# GS_V1.net
KiCad netlist of a schematic drawn in Altium Designer
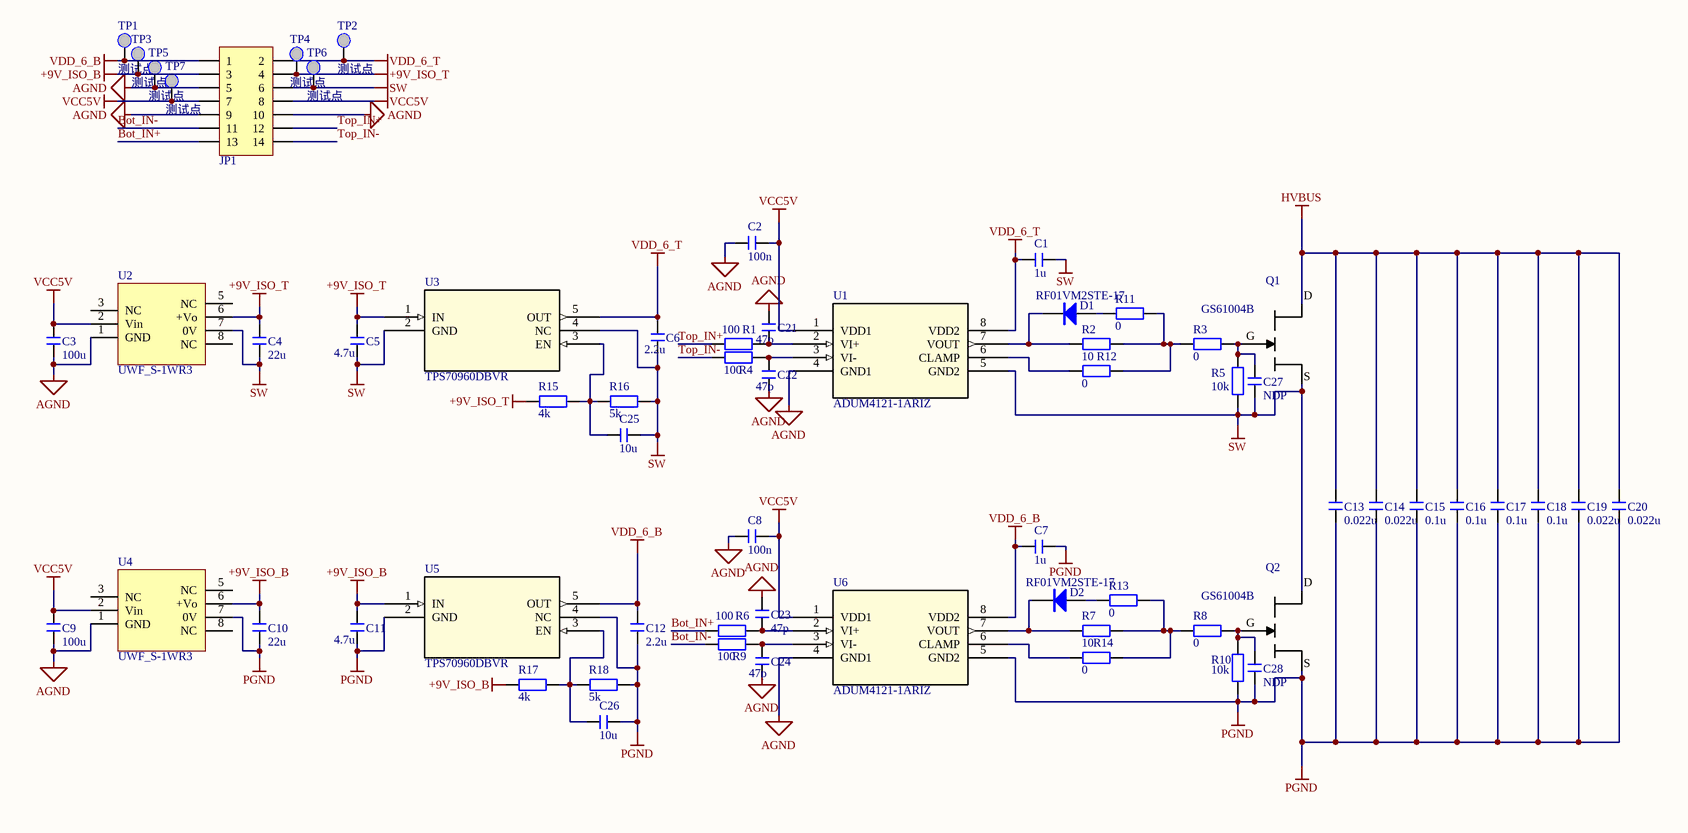
[diagram p0: GS_V1.SchDoc]

(export (version "E")
  (design (tool "Eeschema 10.0.6"))
  (components
    (comp (ref "C1")
      (value "1u")
      (footprint "C 0603_L")
      (description "无极性贴片电容")
      (fields (field (name "版权归属") "源创客"))
      (libsource (lib "3.1   - 电阻-电容-电感") (part "C"))
    )
    (comp (ref "C2")
      (value "100n")
      (footprint "C 0603_L")
      (description "无极性贴片电容")
      (fields (field (name "版权归属") "源创客"))
      (libsource (lib "3.1   - 电阻-电容-电感") (part "C"))
    )
    (comp (ref "C3")
      (value "100u")
      (footprint "C 0805_L")
      (description "无极性贴片电容")
      (fields (field (name "版权归属") "源创客"))
      (libsource (lib "3.1   - 电阻-电容-电感") (part "C"))
    )
    (comp (ref "C4")
      (value "22u")
      (footprint "C 0603_L")
      (description "无极性贴片电容")
      (fields (field (name "版权归属") "源创客"))
      (libsource (lib "3.1   - 电阻-电容-电感") (part "C"))
    )
    (comp (ref "C5")
      (value "4.7u")
      (footprint "C 0603_L")
      (description "无极性贴片电容")
      (fields (field (name "版权归属") "源创客"))
      (libsource (lib "3.1   - 电阻-电容-电感") (part "C"))
    )
    (comp (ref "C6")
      (value "2.2u")
      (footprint "C 0603_L")
      (description "无极性贴片电容")
      (fields (field (name "版权归属") "源创客"))
      (libsource (lib "3.1   - 电阻-电容-电感") (part "C"))
    )
    (comp (ref "C7")
      (value "1u")
      (footprint "C 0603_L")
      (description "无极性贴片电容")
      (fields (field (name "版权归属") "源创客"))
      (libsource (lib "3.1   - 电阻-电容-电感") (part "C"))
    )
    (comp (ref "C8")
      (value "100n")
      (footprint "C 0603_L")
      (description "无极性贴片电容")
      (fields (field (name "版权归属") "源创客"))
      (libsource (lib "3.1   - 电阻-电容-电感") (part "C"))
    )
    (comp (ref "C9")
      (value "100u")
      (footprint "C 0805_L")
      (description "无极性贴片电容")
      (fields (field (name "版权归属") "源创客"))
      (libsource (lib "3.1   - 电阻-电容-电感") (part "C"))
    )
    (comp (ref "C10")
      (value "22u")
      (footprint "C 0603_L")
      (description "无极性贴片电容")
      (fields (field (name "版权归属") "源创客"))
      (libsource (lib "3.1   - 电阻-电容-电感") (part "C"))
    )
    (comp (ref "C11")
      (value "4.7u")
      (footprint "C 0603_L")
      (description "无极性贴片电容")
      (fields (field (name "版权归属") "源创客"))
      (libsource (lib "3.1   - 电阻-电容-电感") (part "C"))
    )
    (comp (ref "C12")
      (value "2.2u")
      (footprint "C 0603_L")
      (description "无极性贴片电容")
      (fields (field (name "版权归属") "源创客"))
      (libsource (lib "3.1   - 电阻-电容-电感") (part "C"))
    )
    (comp (ref "C13")
      (value "0.022u")
      (footprint "C 0805_L")
      (description "无极性贴片电容")
      (fields (field (name "版权归属") "源创客"))
      (libsource (lib "3.1   - 电阻-电容-电感") (part "C"))
    )
    (comp (ref "C14")
      (value "0.022u")
      (footprint "C 0805_L")
      (description "无极性贴片电容")
      (fields (field (name "版权归属") "源创客"))
      (libsource (lib "3.1   - 电阻-电容-电感") (part "C"))
    )
    (comp (ref "C15")
      (value "0.1u")
      (footprint "C 0805_L")
      (description "无极性贴片电容")
      (fields (field (name "版权归属") "源创客"))
      (libsource (lib "3.1   - 电阻-电容-电感") (part "C"))
    )
    (comp (ref "C16")
      (value "0.1u")
      (footprint "C 0805_L")
      (description "无极性贴片电容")
      (fields (field (name "版权归属") "源创客"))
      (libsource (lib "3.1   - 电阻-电容-电感") (part "C"))
    )
    (comp (ref "C17")
      (value "0.1u")
      (footprint "C 0805_L")
      (description "无极性贴片电容")
      (fields (field (name "版权归属") "源创客"))
      (libsource (lib "3.1   - 电阻-电容-电感") (part "C"))
    )
    (comp (ref "C18")
      (value "0.1u")
      (footprint "C 0805_L")
      (description "无极性贴片电容")
      (fields (field (name "版权归属") "源创客"))
      (libsource (lib "3.1   - 电阻-电容-电感") (part "C"))
    )
    (comp (ref "C19")
      (value "0.022u")
      (footprint "C 0805_L")
      (description "无极性贴片电容")
      (fields (field (name "版权归属") "源创客"))
      (libsource (lib "3.1   - 电阻-电容-电感") (part "C"))
    )
    (comp (ref "C20")
      (value "0.022u")
      (footprint "C 0805_L")
      (description "无极性贴片电容")
      (fields (field (name "版权归属") "源创客"))
      (libsource (lib "3.1   - 电阻-电容-电感") (part "C"))
    )
    (comp (ref "C21")
      (value "47p")
      (footprint "C 0603_L")
      (description "无极性贴片电容")
      (fields (field (name "版权归属") "源创客"))
      (libsource (lib "3.1   - 电阻-电容-电感") (part "C"))
    )
    (comp (ref "C22")
      (value "47p")
      (footprint "C 0603_L")
      (description "无极性贴片电容")
      (fields (field (name "版权归属") "源创客"))
      (libsource (lib "3.1   - 电阻-电容-电感") (part "C"))
    )
    (comp (ref "C23")
      (value "47p")
      (footprint "C 0603_L")
      (description "无极性贴片电容")
      (fields (field (name "版权归属") "源创客"))
      (libsource (lib "3.1   - 电阻-电容-电感") (part "C"))
    )
    (comp (ref "C24")
      (value "47p")
      (footprint "C 0603_L")
      (description "无极性贴片电容")
      (fields (field (name "版权归属") "源创客"))
      (libsource (lib "3.1   - 电阻-电容-电感") (part "C"))
    )
    (comp (ref "C25")
      (value "10u")
      (footprint "C 0603_L")
      (description "无极性贴片电容")
      (fields (field (name "版权归属") "源创客"))
      (libsource (lib "3.1   - 电阻-电容-电感") (part "C"))
    )
    (comp (ref "C26")
      (value "10u")
      (footprint "C 0603_L")
      (description "无极性贴片电容")
      (fields (field (name "版权归属") "源创客"))
      (libsource (lib "3.1   - 电阻-电容-电感") (part "C"))
    )
    (comp (ref "C27")
      (value "NDP")
      (footprint "C 0603_L")
      (description "无极性贴片电容")
      (fields (field (name "版权归属") "源创客"))
      (libsource (lib "3.1   - 电阻-电容-电感") (part "C"))
    )
    (comp (ref "C28")
      (value "NDP")
      (footprint "C 0603_L")
      (description "无极性贴片电容")
      (fields (field (name "版权归属") "源创客"))
      (libsource (lib "3.1   - 电阻-电容-电感") (part "C"))
    )
    (comp (ref "D1")
      (value "RF01VM2STE-17")
      (footprint "SOD-323")
      (description "肖特基二极管")
      (fields (field (name "版权归属") "源创客"))
      (libsource (lib "8.1   - 二极管-整流桥") (part "1N5819"))
    )
    (comp (ref "D2")
      (value "RF01VM2STE-17")
      (footprint "SOD-323")
      (description "肖特基二极管")
      (fields (field (name "版权归属") "源创客"))
      (libsource (lib "8.1   - 二极管-整流桥") (part "1N5819"))
    )
    (comp (ref "JP1")
      (value "Header 2X7")
      (footprint "HDR2.54-LI-2x7P")
      (description "7*2P接插件")
      (fields (field (name "版权归属") "源创客"))
      (libsource (lib "4.6   - 接插件-脚距2.54") (part "Header 7X2"))
    )
    (comp (ref "Q1")
      (value "GS61004B")
      (footprint "GS61004B")
      (description "GAN TRANS E-MODE 100V")
      (libsource (lib "GANSYS_ALTIUM_SYMBOL_20220525") (part "GS61004B"))
    )
    (comp (ref "Q2")
      (value "GS61004B")
      (footprint "GS61004B")
      (description "GAN TRANS E-MODE 100V")
      (libsource (lib "GANSYS_ALTIUM_SYMBOL_20220525") (part "GS61004B"))
    )
    (comp (ref "R1")
      (value "100")
      (footprint "R 0603_L")
      (description "贴片电阻")
      (fields (field (name "版权归属") "源创客"))
      (libsource (lib "3.1   - 电阻-电容-电感") (part "R"))
    )
    (comp (ref "R2")
      (value "10")
      (footprint "R 0603_L")
      (description "贴片电阻")
      (fields (field (name "版权归属") "源创客"))
      (libsource (lib "3.1   - 电阻-电容-电感") (part "R"))
    )
    (comp (ref "R3")
      (value "0")
      (footprint "R 0603_L")
      (description "贴片电阻")
      (fields (field (name "版权归属") "源创客"))
      (libsource (lib "3.1   - 电阻-电容-电感") (part "R"))
    )
    (comp (ref "R4")
      (value "100")
      (footprint "R 0603_L")
      (description "贴片电阻")
      (fields (field (name "版权归属") "源创客"))
      (libsource (lib "3.1   - 电阻-电容-电感") (part "R"))
    )
    (comp (ref "R5")
      (value "10k")
      (footprint "R 0603_L")
      (description "贴片电阻")
      (fields (field (name "版权归属") "源创客"))
      (libsource (lib "3.1   - 电阻-电容-电感") (part "R"))
    )
    (comp (ref "R6")
      (value "100")
      (footprint "R 0603_L")
      (description "贴片电阻")
      (fields (field (name "版权归属") "源创客"))
      (libsource (lib "3.1   - 电阻-电容-电感") (part "R"))
    )
    (comp (ref "R7")
      (value "10")
      (footprint "R 0603_L")
      (description "贴片电阻")
      (fields (field (name "版权归属") "源创客"))
      (libsource (lib "3.1   - 电阻-电容-电感") (part "R"))
    )
    (comp (ref "R8")
      (value "0")
      (footprint "R 0603_L")
      (description "贴片电阻")
      (fields (field (name "版权归属") "源创客"))
      (libsource (lib "3.1   - 电阻-电容-电感") (part "R"))
    )
    (comp (ref "R9")
      (value "100")
      (footprint "R 0603_L")
      (description "贴片电阻")
      (fields (field (name "版权归属") "源创客"))
      (libsource (lib "3.1   - 电阻-电容-电感") (part "R"))
    )
    (comp (ref "R10")
      (value "10k")
      (footprint "R 0603_L")
      (description "贴片电阻")
      (fields (field (name "版权归属") "源创客"))
      (libsource (lib "3.1   - 电阻-电容-电感") (part "R"))
    )
    (comp (ref "R11")
      (value "0")
      (footprint "R 0603_L")
      (description "贴片电阻")
      (fields (field (name "版权归属") "源创客"))
      (libsource (lib "3.1   - 电阻-电容-电感") (part "R"))
    )
    (comp (ref "R12")
      (value "0")
      (footprint "R 0603_L")
      (description "贴片电阻")
      (fields (field (name "版权归属") "源创客"))
      (libsource (lib "3.1   - 电阻-电容-电感") (part "R"))
    )
    (comp (ref "R13")
      (value "0")
      (footprint "R 0603_L")
      (description "贴片电阻")
      (fields (field (name "版权归属") "源创客"))
      (libsource (lib "3.1   - 电阻-电容-电感") (part "R"))
    )
    (comp (ref "R14")
      (value "0")
      (footprint "R 0603_L")
      (description "贴片电阻")
      (fields (field (name "版权归属") "源创客"))
      (libsource (lib "3.1   - 电阻-电容-电感") (part "R"))
    )
    (comp (ref "R15")
      (value "4k")
      (footprint "R 0603_L")
      (description "贴片电阻")
      (fields (field (name "版权归属") "源创客"))
      (libsource (lib "3.1   - 电阻-电容-电感") (part "R"))
    )
    (comp (ref "R16")
      (value "5k")
      (footprint "R 0603_L")
      (description "贴片电阻")
      (fields (field (name "版权归属") "源创客"))
      (libsource (lib "3.1   - 电阻-电容-电感") (part "R"))
    )
    (comp (ref "R17")
      (value "4k")
      (footprint "R 0603_L")
      (description "贴片电阻")
      (fields (field (name "版权归属") "源创客"))
      (libsource (lib "3.1   - 电阻-电容-电感") (part "R"))
    )
    (comp (ref "R18")
      (value "5k")
      (footprint "R 0603_L")
      (description "贴片电阻")
      (fields (field (name "版权归属") "源创客"))
      (libsource (lib "3.1   - 电阻-电容-电感") (part "R"))
    )
    (comp (ref "TP1") (value "测试点") (footprint "tp32") (libsource (lib "USB302") (part "TestPoint")))
    (comp (ref "TP2") (value "测试点") (footprint "tp32") (libsource (lib "USB302") (part "TestPoint")))
    (comp (ref "TP3") (value "测试点") (footprint "tp32") (libsource (lib "USB302") (part "TestPoint")))
    (comp (ref "TP4") (value "测试点") (footprint "tp32") (libsource (lib "USB302") (part "TestPoint")))
    (comp (ref "TP5") (value "测试点") (footprint "tp32") (libsource (lib "USB302") (part "TestPoint")))
    (comp (ref "TP6") (value "测试点") (footprint "tp32") (libsource (lib "USB302") (part "TestPoint")))
    (comp (ref "TP7") (value "测试点") (footprint "tp32") (libsource (lib "USB302") (part "TestPoint")))
    (comp (ref "U1")
      (value "ADUM4121-1ARIZ")
      (footprint "RI-8-1_ADI")
      (description "No Description Available")
      (libsource (lib "ADUM4121-1ARIZ") (part "ADUM4121-1ARIZ"))
    )
    (comp (ref "U2")
      (value "UWF_S-1WR3")
      (footprint "UWF_S-1WR3")
      (libsource (lib "UWF_S-1WR3") (part "UWF_S-1WR3"))
    )
    (comp (ref "U3")
      (value "TPS70960DBVR")
      (footprint "DBV5_TEX")
      (description "No Description Available")
      (libsource (lib "TPS70960DBVR") (part "TPS70960DBVR"))
    )
    (comp (ref "U4")
      (value "UWF_S-1WR3")
      (footprint "UWF_S-1WR3")
      (libsource (lib "UWF_S-1WR3") (part "UWF_S-1WR3"))
    )
    (comp (ref "U5")
      (value "TPS70960DBVR")
      (footprint "DBV5_TEX")
      (description "No Description Available")
      (libsource (lib "TPS70960DBVR") (part "TPS70960DBVR"))
    )
    (comp (ref "U6")
      (value "ADUM4121-1ARIZ")
      (footprint "RI-8-1_ADI")
      (description "No Description Available")
      (libsource (lib "ADUM4121-1ARIZ") (part "ADUM4121-1ARIZ"))
    )
  )
  (nets
    (net (code "1") (name "+9V_ISO_B") (class "Default")
      (node (ref "C10") (pin "2") (pinfunction "2_2") (pintype "passive"))
      (node (ref "C11") (pin "2") (pinfunction "2_2") (pintype "passive"))
      (node (ref "JP1") (pin "3") (pinfunction "3_3") (pintype "passive"))
      (node (ref "R17") (pin "2") (pinfunction "2_2") (pintype "passive"))
      (node (ref "TP3") (pin "1") (pintype "passive"))
      (node (ref "U4") (pin "6") (pinfunction "+Vo_6") (pintype "passive"))
      (node (ref "U5") (pin "1") (pinfunction "IN_1") (pintype "input"))
    )
    (net (code "2") (name "+9V_ISO_T") (class "Default")
      (node (ref "C4") (pin "2") (pinfunction "2_2") (pintype "passive"))
      (node (ref "C5") (pin "2") (pinfunction "2_2") (pintype "passive"))
      (node (ref "JP1") (pin "4") (pinfunction "4_4") (pintype "passive"))
      (node (ref "R15") (pin "2") (pinfunction "2_2") (pintype "passive"))
      (node (ref "TP4") (pin "1") (pintype "passive"))
      (node (ref "U2") (pin "6") (pinfunction "+Vo_6") (pintype "passive"))
      (node (ref "U3") (pin "1") (pinfunction "IN_1") (pintype "input"))
    )
    (net (code "3") (name "/Bot_IN+") (class "Default")
      (node (ref "JP1") (pin "13") (pinfunction "13_13") (pintype "passive"))
      (node (ref "R6") (pin "1") (pinfunction "1_1") (pintype "passive"))
    )
    (net (code "4") (name "/Bot_IN-") (class "Default")
      (node (ref "JP1") (pin "11") (pinfunction "11_11") (pintype "passive"))
      (node (ref "R9") (pin "1") (pinfunction "1_1") (pintype "passive"))
    )
    (net (code "5") (name "/Top_IN+") (class "Default")
      (node (ref "JP1") (pin "12") (pinfunction "12_12") (pintype "passive"))
      (node (ref "R1") (pin "1") (pinfunction "1_1") (pintype "passive"))
    )
    (net (code "6") (name "/Top_IN-") (class "Default")
      (node (ref "JP1") (pin "14") (pinfunction "14_14") (pintype "passive"))
      (node (ref "R4") (pin "1") (pinfunction "1_1") (pintype "passive"))
    )
    (net (code "7") (name "AGND") (class "Default")
      (node (ref "C2") (pin "2") (pinfunction "2_2") (pintype "passive"))
      (node (ref "C21") (pin "2") (pinfunction "2_2") (pintype "passive"))
      (node (ref "C22") (pin "1") (pinfunction "1_1") (pintype "passive"))
      (node (ref "C23") (pin "1") (pinfunction "1_1") (pintype "passive"))
      (node (ref "C24") (pin "1") (pinfunction "1_1") (pintype "passive"))
      (node (ref "C3") (pin "1") (pinfunction "1_1") (pintype "passive"))
      (node (ref "C8") (pin "2") (pinfunction "2_2") (pintype "passive"))
      (node (ref "C9") (pin "1") (pinfunction "1_1") (pintype "passive"))
      (node (ref "JP1") (pin "10") (pinfunction "10_10") (pintype "passive"))
      (node (ref "JP1") (pin "5") (pinfunction "5_5") (pintype "passive"))
      (node (ref "JP1") (pin "9") (pinfunction "9_9") (pintype "passive"))
      (node (ref "TP5") (pin "1") (pintype "passive"))
      (node (ref "U1") (pin "4") (pinfunction "GND1_4") (pintype "power_in"))
      (node (ref "U2") (pin "1") (pinfunction "GND_1") (pintype "passive"))
      (node (ref "U4") (pin "1") (pinfunction "GND_1") (pintype "passive"))
      (node (ref "U6") (pin "4") (pinfunction "GND1_4") (pintype "power_in"))
    )
    (net (code "8") (name "HVBUS") (class "Default")
      (node (ref "C13") (pin "2") (pinfunction "2_2") (pintype "passive"))
      (node (ref "C14") (pin "2") (pinfunction "2_2") (pintype "passive"))
      (node (ref "C15") (pin "2") (pinfunction "2_2") (pintype "passive"))
      (node (ref "C16") (pin "2") (pinfunction "2_2") (pintype "passive"))
      (node (ref "C17") (pin "2") (pinfunction "2_2") (pintype "passive"))
      (node (ref "C18") (pin "2") (pinfunction "2_2") (pintype "passive"))
      (node (ref "C19") (pin "2") (pinfunction "2_2") (pintype "passive"))
      (node (ref "C20") (pin "2") (pinfunction "2_2") (pintype "passive"))
      (node (ref "Q1") (pin "D") (pinfunction "D_D") (pintype "passive"))
    )
    (net (code "9") (name "Net-(C27-Pad1)") (class "Default")
      (node (ref "C27") (pin "1") (pinfunction "1_1") (pintype "passive"))
      (node (ref "Q1") (pin "G") (pinfunction "G_G") (pintype "passive"))
      (node (ref "R3") (pin "2") (pinfunction "2_2") (pintype "passive"))
      (node (ref "R5") (pin "2") (pinfunction "2_2") (pintype "passive"))
    )
    (net (code "10") (name "Net-(C28-Pad1)") (class "Default")
      (node (ref "C28") (pin "1") (pinfunction "1_1") (pintype "passive"))
      (node (ref "Q2") (pin "G") (pinfunction "G_G") (pintype "passive"))
      (node (ref "R10") (pin "2") (pinfunction "2_2") (pintype "passive"))
      (node (ref "R8") (pin "2") (pinfunction "2_2") (pintype "passive"))
    )
    (net (code "11") (name "Net-(D1-A)") (class "Default")
      (node (ref "D1") (pin "1") (pinfunction "A_1") (pintype "passive"))
      (node (ref "R11") (pin "1") (pinfunction "1_1") (pintype "passive"))
    )
    (net (code "12") (name "Net-(D1-K)") (class "Default")
      (node (ref "D1") (pin "2") (pinfunction "K_2") (pintype "passive"))
      (node (ref "R2") (pin "1") (pinfunction "1_1") (pintype "passive"))
      (node (ref "U1") (pin "7") (pinfunction "VOUT_7") (pintype "output"))
    )
    (net (code "13") (name "Net-(D2-A)") (class "Default")
      (node (ref "D2") (pin "1") (pinfunction "A_1") (pintype "passive"))
      (node (ref "R13") (pin "1") (pinfunction "1_1") (pintype "passive"))
    )
    (net (code "14") (name "Net-(D2-K)") (class "Default")
      (node (ref "D2") (pin "2") (pinfunction "K_2") (pintype "passive"))
      (node (ref "R7") (pin "1") (pinfunction "1_1") (pintype "passive"))
      (node (ref "U6") (pin "7") (pinfunction "VOUT_7") (pintype "output"))
    )
    (net (code "15") (name "Net-(R11-Pad2)") (class "Default")
      (node (ref "R11") (pin "2") (pinfunction "2_2") (pintype "passive"))
      (node (ref "R12") (pin "2") (pinfunction "2_2") (pintype "passive"))
      (node (ref "R2") (pin "2") (pinfunction "2_2") (pintype "passive"))
      (node (ref "R3") (pin "1") (pinfunction "1_1") (pintype "passive"))
    )
    (net (code "16") (name "Net-(R13-Pad2)") (class "Default")
      (node (ref "R13") (pin "2") (pinfunction "2_2") (pintype "passive"))
      (node (ref "R14") (pin "2") (pinfunction "2_2") (pintype "passive"))
      (node (ref "R7") (pin "2") (pinfunction "2_2") (pintype "passive"))
      (node (ref "R8") (pin "1") (pinfunction "1_1") (pintype "passive"))
    )
    (net (code "17") (name "Net-(U1-CLAMP)") (class "Default")
      (node (ref "R12") (pin "1") (pinfunction "1_1") (pintype "passive"))
      (node (ref "U1") (pin "6") (pinfunction "CLAMP_6") (pintype "passive"))
    )
    (net (code "18") (name "Net-(U1-VI+)") (class "Default")
      (node (ref "C21") (pin "1") (pinfunction "1_1") (pintype "passive"))
      (node (ref "R1") (pin "2") (pinfunction "2_2") (pintype "passive"))
      (node (ref "U1") (pin "2") (pinfunction "VI+_2") (pintype "input"))
    )
    (net (code "19") (name "Net-(U1-VI-)") (class "Default")
      (node (ref "C22") (pin "2") (pinfunction "2_2") (pintype "passive"))
      (node (ref "R4") (pin "2") (pinfunction "2_2") (pintype "passive"))
      (node (ref "U1") (pin "3") (pinfunction "VI-_3") (pintype "input"))
    )
    (net (code "20") (name "Net-(U3-EN)") (class "Default")
      (node (ref "C25") (pin "2") (pinfunction "2_2") (pintype "passive"))
      (node (ref "R15") (pin "1") (pinfunction "1_1") (pintype "passive"))
      (node (ref "R16") (pin "2") (pinfunction "2_2") (pintype "passive"))
      (node (ref "U3") (pin "3") (pinfunction "EN_3") (pintype "input"))
    )
    (net (code "21") (name "Net-(U5-EN)") (class "Default")
      (node (ref "C26") (pin "2") (pinfunction "2_2") (pintype "passive"))
      (node (ref "R17") (pin "1") (pinfunction "1_1") (pintype "passive"))
      (node (ref "R18") (pin "2") (pinfunction "2_2") (pintype "passive"))
      (node (ref "U5") (pin "3") (pinfunction "EN_3") (pintype "input"))
    )
    (net (code "22") (name "Net-(U6-CLAMP)") (class "Default")
      (node (ref "R14") (pin "1") (pinfunction "1_1") (pintype "passive"))
      (node (ref "U6") (pin "6") (pinfunction "CLAMP_6") (pintype "passive"))
    )
    (net (code "23") (name "Net-(U6-VI+)") (class "Default")
      (node (ref "C23") (pin "2") (pinfunction "2_2") (pintype "passive"))
      (node (ref "R6") (pin "2") (pinfunction "2_2") (pintype "passive"))
      (node (ref "U6") (pin "2") (pinfunction "VI+_2") (pintype "input"))
    )
    (net (code "24") (name "Net-(U6-VI-)") (class "Default")
      (node (ref "C24") (pin "2") (pinfunction "2_2") (pintype "passive"))
      (node (ref "R9") (pin "2") (pinfunction "2_2") (pintype "passive"))
      (node (ref "U6") (pin "3") (pinfunction "VI-_3") (pintype "input"))
    )
    (net (code "25") (name "PGND") (class "Default")
      (node (ref "C10") (pin "1") (pinfunction "1_1") (pintype "passive"))
      (node (ref "C11") (pin "1") (pinfunction "1_1") (pintype "passive"))
      (node (ref "C12") (pin "1") (pinfunction "1_1") (pintype "passive"))
      (node (ref "C13") (pin "1") (pinfunction "1_1") (pintype "passive"))
      (node (ref "C14") (pin "1") (pinfunction "1_1") (pintype "passive"))
      (node (ref "C15") (pin "1") (pinfunction "1_1") (pintype "passive"))
      (node (ref "C16") (pin "1") (pinfunction "1_1") (pintype "passive"))
      (node (ref "C17") (pin "1") (pinfunction "1_1") (pintype "passive"))
      (node (ref "C18") (pin "1") (pinfunction "1_1") (pintype "passive"))
      (node (ref "C19") (pin "1") (pinfunction "1_1") (pintype "passive"))
      (node (ref "C20") (pin "1") (pinfunction "1_1") (pintype "passive"))
      (node (ref "C26") (pin "1") (pinfunction "1_1") (pintype "passive"))
      (node (ref "C28") (pin "2") (pinfunction "2_2") (pintype "passive"))
      (node (ref "C7") (pin "2") (pinfunction "2_2") (pintype "passive"))
      (node (ref "Q2") (pin "S") (pinfunction "S_S") (pintype "passive"))
      (node (ref "R10") (pin "1") (pinfunction "1_1") (pintype "passive"))
      (node (ref "R18") (pin "1") (pinfunction "1_1") (pintype "passive"))
      (node (ref "U4") (pin "7") (pinfunction "0V_7") (pintype "passive"))
      (node (ref "U5") (pin "2") (pinfunction "GND_2") (pintype "power_in"))
      (node (ref "U5") (pin "4") (pinfunction "NC_4") (pintype "passive"))
      (node (ref "U6") (pin "5") (pinfunction "GND2_5") (pintype "power_in"))
    )
    (net (code "26") (name "SW") (class "Default")
      (node (ref "C1") (pin "2") (pinfunction "2_2") (pintype "passive"))
      (node (ref "C25") (pin "1") (pinfunction "1_1") (pintype "passive"))
      (node (ref "C27") (pin "2") (pinfunction "2_2") (pintype "passive"))
      (node (ref "C4") (pin "1") (pinfunction "1_1") (pintype "passive"))
      (node (ref "C5") (pin "1") (pinfunction "1_1") (pintype "passive"))
      (node (ref "C6") (pin "1") (pinfunction "1_1") (pintype "passive"))
      (node (ref "JP1") (pin "6") (pinfunction "6_6") (pintype "passive"))
      (node (ref "Q1") (pin "S") (pinfunction "S_S") (pintype "passive"))
      (node (ref "Q2") (pin "D") (pinfunction "D_D") (pintype "passive"))
      (node (ref "R16") (pin "1") (pinfunction "1_1") (pintype "passive"))
      (node (ref "R5") (pin "1") (pinfunction "1_1") (pintype "passive"))
      (node (ref "TP6") (pin "1") (pintype "passive"))
      (node (ref "U1") (pin "5") (pinfunction "GND2_5") (pintype "power_in"))
      (node (ref "U2") (pin "7") (pinfunction "0V_7") (pintype "passive"))
      (node (ref "U3") (pin "2") (pinfunction "GND_2") (pintype "power_in"))
      (node (ref "U3") (pin "4") (pinfunction "NC_4") (pintype "passive"))
    )
    (net (code "27") (name "VCC5V") (class "Default")
      (node (ref "C2") (pin "1") (pinfunction "1_1") (pintype "passive"))
      (node (ref "C3") (pin "2") (pinfunction "2_2") (pintype "passive"))
      (node (ref "C8") (pin "1") (pinfunction "1_1") (pintype "passive"))
      (node (ref "C9") (pin "2") (pinfunction "2_2") (pintype "passive"))
      (node (ref "JP1") (pin "7") (pinfunction "7_7") (pintype "passive"))
      (node (ref "JP1") (pin "8") (pinfunction "8_8") (pintype "passive"))
      (node (ref "TP7") (pin "1") (pintype "passive"))
      (node (ref "U1") (pin "1") (pinfunction "VDD1_1") (pintype "power_in"))
      (node (ref "U2") (pin "2") (pinfunction "Vin_2") (pintype "passive"))
      (node (ref "U4") (pin "2") (pinfunction "Vin_2") (pintype "passive"))
      (node (ref "U6") (pin "1") (pinfunction "VDD1_1") (pintype "power_in"))
    )
    (net (code "28") (name "VDD_6_B") (class "Default")
      (node (ref "C12") (pin "2") (pinfunction "2_2") (pintype "passive"))
      (node (ref "C7") (pin "1") (pinfunction "1_1") (pintype "passive"))
      (node (ref "JP1") (pin "1") (pinfunction "1_1") (pintype "passive"))
      (node (ref "TP1") (pin "1") (pintype "passive"))
      (node (ref "U5") (pin "5") (pinfunction "OUT_5") (pintype "output"))
      (node (ref "U6") (pin "8") (pinfunction "VDD2_8") (pintype "power_in"))
    )
    (net (code "29") (name "VDD_6_T") (class "Default")
      (node (ref "C1") (pin "1") (pinfunction "1_1") (pintype "passive"))
      (node (ref "C6") (pin "2") (pinfunction "2_2") (pintype "passive"))
      (node (ref "JP1") (pin "2") (pinfunction "2_2") (pintype "passive"))
      (node (ref "TP2") (pin "1") (pintype "passive"))
      (node (ref "U1") (pin "8") (pinfunction "VDD2_8") (pintype "power_in"))
      (node (ref "U3") (pin "5") (pinfunction "OUT_5") (pintype "output"))
    )
    (net (code "30") (name "unconnected-(U2-NC-Pad3)") (class "Default")
      (node (ref "U2") (pin "3") (pinfunction "NC_3") (pintype "passive"))
    )
    (net (code "31") (name "unconnected-(U2-NC-Pad5)") (class "Default")
      (node (ref "U2") (pin "5") (pinfunction "NC_5") (pintype "passive"))
    )
    (net (code "32") (name "unconnected-(U2-NC-Pad8)") (class "Default")
      (node (ref "U2") (pin "8") (pinfunction "NC_8") (pintype "passive"))
    )
    (net (code "33") (name "unconnected-(U4-NC-Pad3)") (class "Default")
      (node (ref "U4") (pin "3") (pinfunction "NC_3") (pintype "passive"))
    )
    (net (code "34") (name "unconnected-(U4-NC-Pad5)") (class "Default")
      (node (ref "U4") (pin "5") (pinfunction "NC_5") (pintype "passive"))
    )
    (net (code "35") (name "unconnected-(U4-NC-Pad8)") (class "Default")
      (node (ref "U4") (pin "8") (pinfunction "NC_8") (pintype "passive"))
    )
  )
)
